# 6WP_arduino_DFPlayer.net
KiCad netlist of a schematic drawn in EAGLE
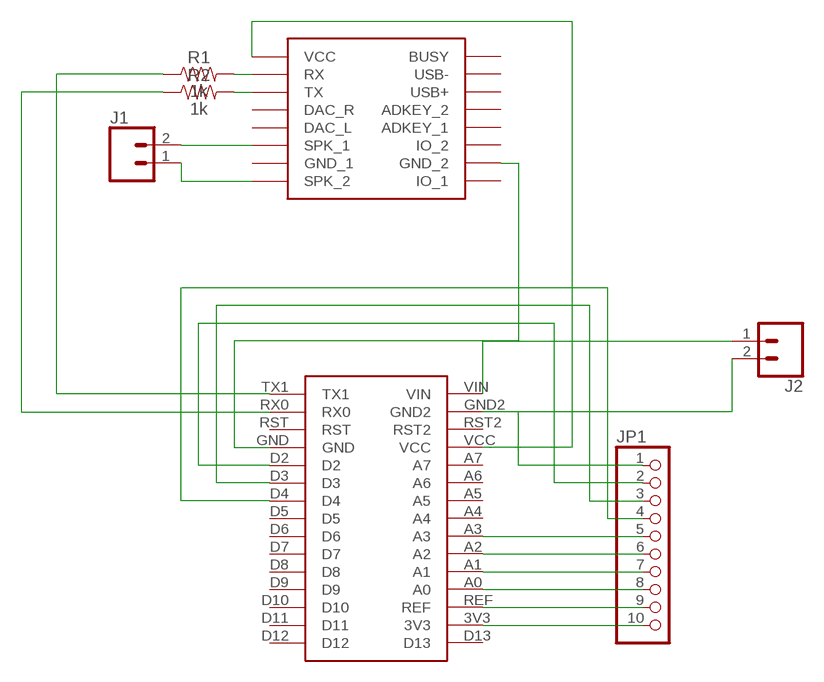
[diagram p0: schematic, sheet 1]

(export (version "E")
  (design (tool "Eeschema 10.0.6"))
  (components
    (comp (ref "A3")
      (value "ARDUINONANO")
      (footprint "eagle-import:ARDUINONANO")
      (libsource (lib "eagle-import") (part "ARDUINONANO"))
    )
    (comp (ref "J1")
      (value "CONN_02JST-PTH-2")
      (footprint "eagle-import:JST-2-PTH")
      (libsource (lib "eagle-import") (part "CONN_02JST-PTH-2"))
    )
    (comp (ref "J2")
      (value "CONN_02JST-PTH-2")
      (footprint "eagle-import:JST-2-PTH")
      (libsource (lib "eagle-import") (part "CONN_02JST-PTH-2"))
    )
    (comp (ref "JP1")
      (value "PINHD-1X10/90")
      (footprint "eagle-import:1X10_90")
      (libsource (lib "eagle-import") (part "PINHD-1X10/90"))
    )
    (comp (ref "R1")
      (value "1k")
      (footprint "eagle-import:AXIAL-0.3")
      (libsource (lib "eagle-import") (part "1KOHM-HORIZ-1/4W-1%"))
    )
    (comp (ref "R2")
      (value "1k")
      (footprint "eagle-import:AXIAL-0.3")
      (libsource (lib "eagle-import") (part "1KOHM-HORIZ-1/4W-1%"))
    )
    (comp (ref "U$1")
      (value "DFPLAYER")
      (footprint "eagle-import:DFPLAYER")
      (libsource (lib "eagle-import") (part "DFPLAYER"))
    )
  )
  (nets
    (net (code "1") (name "Net-(A3-Pad3V3)") (class "Default")
      (node (ref "A3") (pin "3V3") (pinfunction "3V3_3V3") (pintype "bidirectional"))
      (node (ref "JP1") (pin "10") (pinfunction "10_10") (pintype "passive"))
    )
    (net (code "2") (name "Net-(A3-PadA0)") (class "Default")
      (node (ref "A3") (pin "A0") (pinfunction "A0_A0") (pintype "bidirectional"))
      (node (ref "JP1") (pin "8") (pinfunction "8_8") (pintype "passive"))
    )
    (net (code "3") (name "Net-(A3-PadA1)") (class "Default")
      (node (ref "A3") (pin "A1") (pinfunction "A1_A1") (pintype "bidirectional"))
      (node (ref "JP1") (pin "7") (pinfunction "7_7") (pintype "passive"))
    )
    (net (code "4") (name "Net-(A3-PadA2)") (class "Default")
      (node (ref "A3") (pin "A2") (pinfunction "A2_A2") (pintype "bidirectional"))
      (node (ref "JP1") (pin "6") (pinfunction "6_6") (pintype "passive"))
    )
    (net (code "5") (name "Net-(A3-PadA3)") (class "Default")
      (node (ref "A3") (pin "A3") (pinfunction "A3_A3") (pintype "bidirectional"))
      (node (ref "JP1") (pin "5") (pinfunction "5_5") (pintype "passive"))
    )
    (net (code "6") (name "Net-(A3-PadD2)") (class "Default")
      (node (ref "A3") (pin "D2") (pinfunction "D2_D2") (pintype "bidirectional"))
      (node (ref "JP1") (pin "2") (pinfunction "2_2") (pintype "passive"))
    )
    (net (code "7") (name "Net-(A3-PadD3)") (class "Default")
      (node (ref "A3") (pin "D3") (pinfunction "D3_D3") (pintype "bidirectional"))
      (node (ref "JP1") (pin "3") (pinfunction "3_3") (pintype "passive"))
    )
    (net (code "8") (name "Net-(A3-PadD4)") (class "Default")
      (node (ref "A3") (pin "D4") (pinfunction "D4_D4") (pintype "bidirectional"))
      (node (ref "JP1") (pin "4") (pinfunction "4_4") (pintype "passive"))
    )
    (net (code "9") (name "Net-(A3-PadGND)") (class "Default")
      (node (ref "A3") (pin "GND") (pinfunction "GND_GND") (pintype "bidirectional"))
      (node (ref "U$1") (pin "GND_2") (pinfunction "GND_2_GND_2") (pintype "bidirectional"))
    )
    (net (code "10") (name "Net-(A3-PadGND2)") (class "Default")
      (node (ref "A3") (pin "GND2") (pinfunction "GND2_GND2") (pintype "bidirectional"))
      (node (ref "J2") (pin "2") (pinfunction "2_2") (pintype "passive"))
      (node (ref "JP1") (pin "1") (pinfunction "1_1") (pintype "passive"))
    )
    (net (code "11") (name "Net-(A3-PadREF)") (class "Default")
      (node (ref "A3") (pin "REF") (pinfunction "REF_REF") (pintype "bidirectional"))
      (node (ref "JP1") (pin "9") (pinfunction "9_9") (pintype "passive"))
    )
    (net (code "12") (name "Net-(A3-PadVCC)") (class "Default")
      (node (ref "A3") (pin "VCC") (pinfunction "VCC_VCC") (pintype "bidirectional"))
      (node (ref "U$1") (pin "VCC") (pinfunction "VCC_VCC") (pintype "bidirectional"))
    )
    (net (code "13") (name "Net-(A3-PadVIN)") (class "Default")
      (node (ref "A3") (pin "VIN") (pinfunction "VIN_VIN") (pintype "bidirectional"))
      (node (ref "J2") (pin "1") (pinfunction "1_1") (pintype "passive"))
    )
    (net (code "14") (name "Net-(R1-1)") (class "Default")
      (node (ref "A3") (pin "TX1") (pinfunction "TX1_TX1") (pintype "bidirectional"))
      (node (ref "R1") (pin "P$1") (pinfunction "1_P$1") (pintype "passive"))
    )
    (net (code "15") (name "Net-(R1-2)") (class "Default")
      (node (ref "R1") (pin "P$2") (pinfunction "2_P$2") (pintype "passive"))
      (node (ref "U$1") (pin "RX") (pinfunction "RX_RX") (pintype "bidirectional"))
    )
    (net (code "16") (name "Net-(R2-1)") (class "Default")
      (node (ref "A3") (pin "RX0") (pinfunction "RX0_RX0") (pintype "bidirectional"))
      (node (ref "R2") (pin "P$1") (pinfunction "1_P$1") (pintype "passive"))
    )
    (net (code "17") (name "Net-(R2-2)") (class "Default")
      (node (ref "R2") (pin "P$2") (pinfunction "2_P$2") (pintype "passive"))
      (node (ref "U$1") (pin "TX") (pinfunction "TX_TX") (pintype "bidirectional"))
    )
    (net (code "18") (name "Net-(U$1-SPK_1)") (class "Default")
      (node (ref "J1") (pin "2") (pinfunction "2_2") (pintype "passive"))
      (node (ref "U$1") (pin "SPK1") (pinfunction "SPK_1_SPK1") (pintype "bidirectional"))
    )
    (net (code "19") (name "Net-(U$1-SPK_2)") (class "Default")
      (node (ref "J1") (pin "1") (pinfunction "1_1") (pintype "passive"))
      (node (ref "U$1") (pin "SPK2") (pinfunction "SPK_2_SPK2") (pintype "bidirectional"))
    )
    (net (code "20") (name "unconnected-(A3-PadA4)") (class "Default")
      (node (ref "A3") (pin "A4") (pinfunction "A4_A4") (pintype "bidirectional"))
    )
    (net (code "21") (name "unconnected-(A3-PadA5)") (class "Default")
      (node (ref "A3") (pin "A5") (pinfunction "A5_A5") (pintype "bidirectional"))
    )
    (net (code "22") (name "unconnected-(A3-PadA6)") (class "Default")
      (node (ref "A3") (pin "A6") (pinfunction "A6_A6") (pintype "bidirectional"))
    )
    (net (code "23") (name "unconnected-(A3-PadA7)") (class "Default")
      (node (ref "A3") (pin "A7") (pinfunction "A7_A7") (pintype "bidirectional"))
    )
    (net (code "24") (name "unconnected-(A3-PadD5)") (class "Default")
      (node (ref "A3") (pin "D5") (pinfunction "D5_D5") (pintype "bidirectional"))
    )
    (net (code "25") (name "unconnected-(A3-PadD6)") (class "Default")
      (node (ref "A3") (pin "D6") (pinfunction "D6_D6") (pintype "bidirectional"))
    )
    (net (code "26") (name "unconnected-(A3-PadD7)") (class "Default")
      (node (ref "A3") (pin "D7") (pinfunction "D7_D7") (pintype "bidirectional"))
    )
    (net (code "27") (name "unconnected-(A3-PadD8)") (class "Default")
      (node (ref "A3") (pin "D8") (pinfunction "D8_D8") (pintype "bidirectional"))
    )
    (net (code "28") (name "unconnected-(A3-PadD9)") (class "Default")
      (node (ref "A3") (pin "D9") (pinfunction "D9_D9") (pintype "bidirectional"))
    )
    (net (code "29") (name "unconnected-(A3-PadD10)") (class "Default")
      (node (ref "A3") (pin "D10") (pinfunction "D10_D10") (pintype "bidirectional"))
    )
    (net (code "30") (name "unconnected-(A3-PadD11)") (class "Default")
      (node (ref "A3") (pin "D11") (pinfunction "D11_D11") (pintype "bidirectional"))
    )
    (net (code "31") (name "unconnected-(A3-PadD12)") (class "Default")
      (node (ref "A3") (pin "D12") (pinfunction "D12_D12") (pintype "bidirectional"))
    )
    (net (code "32") (name "unconnected-(A3-PadD13)") (class "Default")
      (node (ref "A3") (pin "D13") (pinfunction "D13_D13") (pintype "bidirectional"))
    )
    (net (code "33") (name "unconnected-(A3-PadRST)") (class "Default")
      (node (ref "A3") (pin "RST") (pinfunction "RST_RST") (pintype "bidirectional"))
    )
    (net (code "34") (name "unconnected-(A3-PadRST2)") (class "Default")
      (node (ref "A3") (pin "RST2") (pinfunction "RST2_RST2") (pintype "bidirectional"))
    )
    (net (code "35") (name "unconnected-(U$1-ADKEY_1-PadADKEY1)") (class "Default")
      (node (ref "U$1") (pin "ADKEY1") (pinfunction "ADKEY_1_ADKEY1") (pintype "bidirectional"))
    )
    (net (code "36") (name "unconnected-(U$1-ADKEY_2-PadADKEY2)") (class "Default")
      (node (ref "U$1") (pin "ADKEY2") (pinfunction "ADKEY_2_ADKEY2") (pintype "bidirectional"))
    )
    (net (code "37") (name "unconnected-(U$1-IO_1-PadIO1)") (class "Default")
      (node (ref "U$1") (pin "IO1") (pinfunction "IO_1_IO1") (pintype "bidirectional"))
    )
    (net (code "38") (name "unconnected-(U$1-IO_2-PadIO2)") (class "Default")
      (node (ref "U$1") (pin "IO2") (pinfunction "IO_2_IO2") (pintype "bidirectional"))
    )
    (net (code "39") (name "unconnected-(U$1-PadBUSY)") (class "Default")
      (node (ref "U$1") (pin "BUSY") (pinfunction "BUSY_BUSY") (pintype "bidirectional"))
    )
    (net (code "40") (name "unconnected-(U$1-PadDAC_L)") (class "Default")
      (node (ref "U$1") (pin "DAC_L") (pinfunction "DAC_L_DAC_L") (pintype "bidirectional"))
    )
    (net (code "41") (name "unconnected-(U$1-PadDAC_R)") (class "Default")
      (node (ref "U$1") (pin "DAC_R") (pinfunction "DAC_R_DAC_R") (pintype "bidirectional"))
    )
    (net (code "42") (name "unconnected-(U$1-PadGND_1)") (class "Default")
      (node (ref "U$1") (pin "GND_1") (pinfunction "GND_1_GND_1") (pintype "bidirectional"))
    )
    (net (code "43") (name "unconnected-(U$1-PadUSB+)") (class "Default")
      (node (ref "U$1") (pin "USB+") (pinfunction "USB+_USB+") (pintype "bidirectional"))
    )
    (net (code "44") (name "unconnected-(U$1-PadUSB-)") (class "Default")
      (node (ref "U$1") (pin "USB-") (pinfunction "USB-_USB-") (pintype "bidirectional"))
    )
  )
)
